# TX_V1_Schematic.net
KiCad netlist of a schematic drawn in Altium Designer
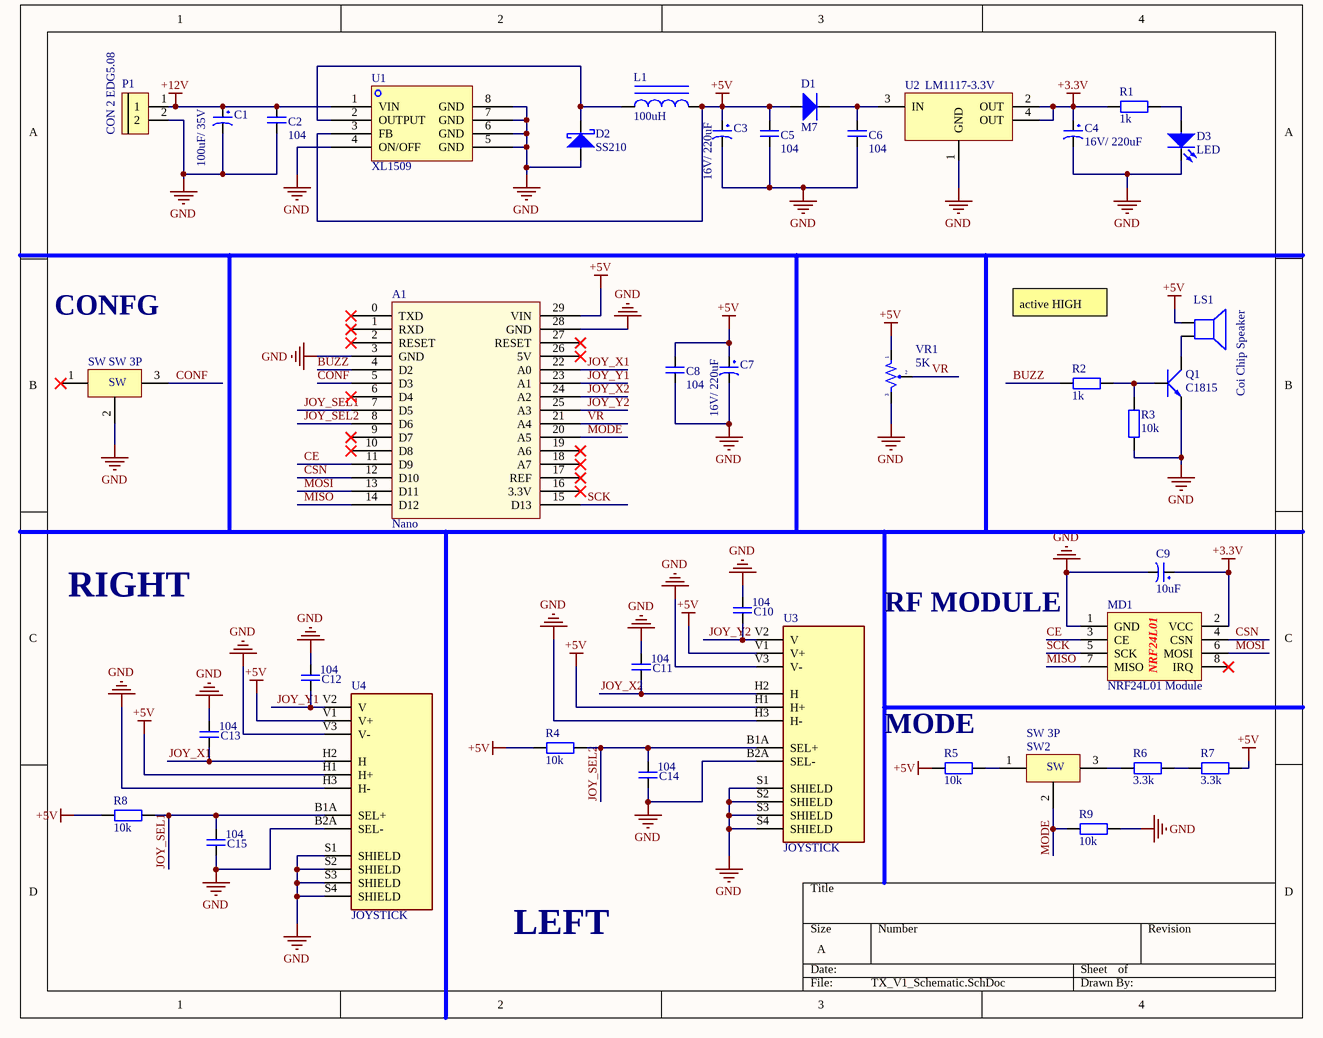
[diagram p0: TX_V1_Schematic.SchDoc]

(export (version "E")
  (design (tool "Eeschema 10.0.6"))
  (components
    (comp (ref "A1")
      (value "Nano")
      (footprint "Arduino nano")
      (libsource (lib "Altium_Lib_by_KhueNguyenCreator") (part "Arduino Nano"))
    )
    (comp (ref "C1")
      (value "100uF/ 35V")
      (footprint "CAP SMD ALUMINUM D8")
      (libsource (lib "Electronic4u") (part "Cap_Polar"))
    )
    (comp (ref "C2")
      (value "104")
      (footprint "SM-0805")
      (libsource (lib "Electronic4u") (part "Cap_Non-Polar"))
    )
    (comp (ref "C3")
      (value "16V/ 220uF")
      (footprint "CAP SMD ALUMINUM D8")
      (libsource (lib "Electronic4u") (part "Cap_Polar"))
    )
    (comp (ref "C4")
      (value "16V/ 220uF")
      (footprint "CAP SMD ALUMINUM D8")
      (libsource (lib "Electronic4u") (part "Cap_Polar"))
    )
    (comp (ref "C5")
      (value "104")
      (footprint "SM-0805")
      (libsource (lib "Electronic4u") (part "Cap_Non-Polar"))
    )
    (comp (ref "C6")
      (value "104")
      (footprint "SM-0805")
      (libsource (lib "Electronic4u") (part "Cap_Non-Polar"))
    )
    (comp (ref "C7")
      (value "16V/ 220uF")
      (footprint "CAP SMD ALUMINUM D8")
      (libsource (lib "Electronic4u") (part "Cap_Polar"))
    )
    (comp (ref "C8")
      (value "104")
      (footprint "SM-0805")
      (libsource (lib "Electronic4u") (part "Cap_Non-Polar"))
    )
    (comp (ref "C9")
      (value "10uF")
      (footprint "tu hoa 8mm")
      (description "Cắm")
      (libsource (lib "Altium_Lib_by_KhueNguyenCreator") (part "Tu Hoa 100uF 35V 8x11"))
    )
    (comp (ref "C10")
      (value "104")
      (footprint "SM-0805")
      (libsource (lib "Electronic4u") (part "Cap_Non-Polar"))
    )
    (comp (ref "C11")
      (value "104")
      (footprint "SM-0805")
      (libsource (lib "Electronic4u") (part "Cap_Non-Polar"))
    )
    (comp (ref "C12")
      (value "104")
      (footprint "SM-0805")
      (libsource (lib "Electronic4u") (part "Cap_Non-Polar"))
    )
    (comp (ref "C13")
      (value "104")
      (footprint "SM-0805")
      (libsource (lib "Electronic4u") (part "Cap_Non-Polar"))
    )
    (comp (ref "C14")
      (value "104")
      (footprint "SM-0805")
      (libsource (lib "Electronic4u") (part "Cap_Non-Polar"))
    )
    (comp (ref "C15")
      (value "104")
      (footprint "SM-0805")
      (libsource (lib "Electronic4u") (part "Cap_Non-Polar"))
    )
    (comp (ref "D1")
      (value "M7")
      (footprint "DO-214AC")
      (description "Diode Standard")
      (fields (field (name "PART NUMBER") "LED 3 ly Single Colour"))
      (libsource (lib "Electronic4u") (part "Diode Standard"))
    )
    (comp (ref "D2")
      (value "SS210")
      (footprint "DO-214AC")
      (description "Diode Schottky")
      (fields (field (name "PART NUMBER") "LED 3 ly Single Colour"))
      (libsource (lib "Electronic4u") (part "Diode Schottky"))
    )
    (comp (ref "D3")
      (value "LED")
      (footprint "LED-3MM GRE")
      (description "LED Single")
      (libsource (lib "Electronic4u") (part "LED"))
    )
    (comp (ref "L1")
      (value "100uH")
      (footprint "INDUCTOR SMD 7342 7.3X7.3X4.2mm")
      (description "Magnetic-Core Inductor")
      (libsource (lib "Electronic4u") (part "Inductor Iron"))
    )
    (comp (ref "LS1")
      (value "Coi Chip Speaker")
      (footprint "Coi Chip Speacker")
      (description "Còi chip")
      (libsource (lib "Altium_Lib_by_KhueNguyenCreator") (part "Coi Chip Speaker"))
    )
    (comp (ref "MD1")
      (value "NRF24L01 Module")
      (footprint "NRF24L01")
      (libsource (lib "Altium_Lib_by_KhueNguyenCreator") (part "NRF24L01 Module"))
    )
    (comp (ref "P1")
      (value "CON 2 EDG5.08")
      (footprint "CON 2 2EDG5.08")
      (description "Cắm")
      (libsource (lib "Altium_Lib_by_KhueNguyenCreator") (part "CON 2 EDG5.08"))
    )
    (comp (ref "Q1")
      (value "C1815")
      (footprint "SOT23B")
      (description "NPN 600mW, ECB")
      (libsource (lib "Electronic4u") (part "C1815"))
    )
    (comp (ref "R1")
      (value "1k")
      (footprint "RESISTOR SMD 0805")
      (libsource (lib "Electronic4u") (part "Resistor"))
    )
    (comp (ref "R2")
      (value "1k")
      (footprint "RESISTOR SMD 0805")
      (libsource (lib "Electronic4u") (part "Resistor"))
    )
    (comp (ref "R3")
      (value "10k")
      (footprint "RESISTOR SMD 0805")
      (libsource (lib "Electronic4u") (part "Resistor"))
    )
    (comp (ref "R4")
      (value "10k")
      (footprint "RESISTOR SMD 0805")
      (libsource (lib "Electronic4u") (part "Resistor"))
    )
    (comp (ref "R5")
      (value "10k")
      (footprint "RESISTOR SMD 0805")
      (libsource (lib "Electronic4u") (part "Resistor"))
    )
    (comp (ref "R6")
      (value "3.3k")
      (footprint "RESISTOR SMD 0805")
      (libsource (lib "Electronic4u") (part "Resistor"))
    )
    (comp (ref "R7")
      (value "3.3k")
      (footprint "RESISTOR SMD 0805")
      (libsource (lib "Electronic4u") (part "Resistor"))
    )
    (comp (ref "R8")
      (value "10k")
      (footprint "RESISTOR SMD 0805")
      (libsource (lib "Electronic4u") (part "Resistor"))
    )
    (comp (ref "R9")
      (value "10k")
      (footprint "RESISTOR SMD 0805")
      (libsource (lib "Electronic4u") (part "Resistor"))
    )
    (comp (ref "SW") (value "SW 3P") (footprint "MTS-102") (libsource (lib "FMS_PcbLib1") (part "SW 3P")))
    (comp (ref "SW2") (value "SW 3P") (footprint "MTS-102") (libsource (lib "FMS_PcbLib1") (part "SW 3P")))
    (comp (ref "U1")
      (value "XL1509")
      (footprint "SOP8")
      (description "IC power sop8")
      (libsource (lib "FMS_PcbLib1") (part "XL1509"))
    )
    (comp (ref "U2")
      (value "LM1117-3.3V")
      (footprint "SOT223-4N")
      (description "800mA Low-Dropout Linear Regulator")
      (fields (field (name "CREATOR") "Nguyen Ba Bien"))
      (libsource (lib "Electronic4u") (part "LM1117"))
    )
    (comp (ref "U3")
      (value "JOYSTICK")
      (footprint "XDCR_COM-09032")
      (description "Thumb Joystick")
      (fields (field (name "MP") "COM-09032"))
      (libsource (lib "FMS_PcbLib1") (part "JOYSTICK"))
    )
    (comp (ref "U4")
      (value "JOYSTICK")
      (footprint "XDCR_COM-09032")
      (description "Thumb Joystick")
      (fields (field (name "MP") "COM-09032"))
      (libsource (lib "FMS_PcbLib1") (part "JOYSTICK"))
    )
    (comp (ref "VR1")
      (value "5K")
      (footprint "Bien Tro Volume Don")
      (description "Cắm")
      (libsource (lib "Altium_Lib_by_KhueNguyenCreator") (part "Triet Ap Don 5k"))
    )
  )
  (nets
    (net (code "1") (name "+3.3V") (class "Default")
      (node (ref "C4") (pin "1") (pinfunction "1_1") (pintype "passive"))
      (node (ref "C9") (pin "1") (pinfunction "1_1") (pintype "passive"))
      (node (ref "MD1") (pin "2") (pinfunction "VCC_2") (pintype "passive"))
      (node (ref "R1") (pin "1") (pinfunction "1_1") (pintype "passive"))
      (node (ref "U2") (pin "2") (pinfunction "OUT_2") (pintype "passive"))
      (node (ref "U2") (pin "4") (pinfunction "OUT_4") (pintype "passive"))
    )
    (net (code "2") (name "+5V") (class "Default")
      (node (ref "A1") (pin "29") (pinfunction "VIN_29") (pintype "passive"))
      (node (ref "C3") (pin "1") (pinfunction "1_1") (pintype "passive"))
      (node (ref "C5") (pin "2") (pinfunction "2_2") (pintype "passive"))
      (node (ref "C7") (pin "1") (pinfunction "1_1") (pintype "passive"))
      (node (ref "C8") (pin "2") (pinfunction "2_2") (pintype "passive"))
      (node (ref "D1") (pin "1") (pinfunction "1_1") (pintype "passive"))
      (node (ref "L1") (pin "2") (pinfunction "2_2") (pintype "passive"))
      (node (ref "LS1") (pin "1") (pinfunction "1_1") (pintype "passive"))
      (node (ref "R4") (pin "1") (pinfunction "1_1") (pintype "passive"))
      (node (ref "R5") (pin "2") (pinfunction "2_2") (pintype "passive"))
      (node (ref "R7") (pin "1") (pinfunction "1_1") (pintype "passive"))
      (node (ref "R8") (pin "1") (pinfunction "1_1") (pintype "passive"))
      (node (ref "U1") (pin "3") (pinfunction "FB_3") (pintype "passive"))
      (node (ref "U3") (pin "H1") (pinfunction "H+_H1") (pintype "passive"))
      (node (ref "U3") (pin "V1") (pinfunction "V+_V1") (pintype "passive"))
      (node (ref "U4") (pin "H1") (pinfunction "H+_H1") (pintype "passive"))
      (node (ref "U4") (pin "V1") (pinfunction "V+_V1") (pintype "passive"))
      (node (ref "VR1") (pin "1") (pinfunction "1_1") (pintype "passive"))
    )
    (net (code "3") (name "+12V") (class "Default")
      (node (ref "C1") (pin "1") (pinfunction "1_1") (pintype "passive"))
      (node (ref "C2") (pin "2") (pinfunction "2_2") (pintype "passive"))
      (node (ref "P1") (pin "1") (pinfunction "1_1") (pintype "passive"))
      (node (ref "U1") (pin "1") (pinfunction "VIN_1") (pintype "passive"))
    )
    (net (code "4") (name "/BUZZ") (class "Default")
      (node (ref "A1") (pin "4") (pinfunction "D2_4") (pintype "passive"))
      (node (ref "R2") (pin "2") (pinfunction "2_2") (pintype "passive"))
    )
    (net (code "5") (name "/CE") (class "Default")
      (node (ref "A1") (pin "11") (pinfunction "D9_11") (pintype "passive"))
      (node (ref "MD1") (pin "3") (pinfunction "CE_3") (pintype "passive"))
    )
    (net (code "6") (name "/CONF") (class "Default")
      (node (ref "A1") (pin "5") (pinfunction "D3_5") (pintype "passive"))
      (node (ref "SW") (pin "3") (pinfunction "3_3") (pintype "passive"))
    )
    (net (code "7") (name "/CSN") (class "Default")
      (node (ref "A1") (pin "12") (pinfunction "D10_12") (pintype "passive"))
      (node (ref "MD1") (pin "4") (pinfunction "CSN_4") (pintype "passive"))
    )
    (net (code "8") (name "/JOY_SEL1") (class "Default")
      (node (ref "A1") (pin "7") (pinfunction "D5_7") (pintype "passive"))
      (node (ref "C15") (pin "2") (pinfunction "2_2") (pintype "passive"))
      (node (ref "R8") (pin "2") (pinfunction "2_2") (pintype "passive"))
      (node (ref "U4") (pin "B1A") (pinfunction "SEL+_B1A") (pintype "passive"))
    )
    (net (code "9") (name "/JOY_SEL2") (class "Default")
      (node (ref "A1") (pin "8") (pinfunction "D6_8") (pintype "passive"))
      (node (ref "C14") (pin "2") (pinfunction "2_2") (pintype "passive"))
      (node (ref "R4") (pin "2") (pinfunction "2_2") (pintype "passive"))
      (node (ref "U3") (pin "B1A") (pinfunction "SEL+_B1A") (pintype "passive"))
    )
    (net (code "10") (name "/JOY_X1") (class "Default")
      (node (ref "A1") (pin "22") (pinfunction "A0_22") (pintype "passive"))
      (node (ref "C13") (pin "1") (pinfunction "1_1") (pintype "passive"))
      (node (ref "U4") (pin "H2") (pinfunction "H_H2") (pintype "passive"))
    )
    (net (code "11") (name "/JOY_X2") (class "Default")
      (node (ref "A1") (pin "24") (pinfunction "A2_24") (pintype "passive"))
      (node (ref "C11") (pin "1") (pinfunction "1_1") (pintype "passive"))
      (node (ref "U3") (pin "H2") (pinfunction "H_H2") (pintype "passive"))
    )
    (net (code "12") (name "/JOY_Y1") (class "Default")
      (node (ref "A1") (pin "23") (pinfunction "A1_23") (pintype "passive"))
      (node (ref "C12") (pin "1") (pinfunction "1_1") (pintype "passive"))
      (node (ref "U4") (pin "V2") (pinfunction "V_V2") (pintype "passive"))
    )
    (net (code "13") (name "/JOY_Y2") (class "Default")
      (node (ref "A1") (pin "25") (pinfunction "A3_25") (pintype "passive"))
      (node (ref "C10") (pin "1") (pinfunction "1_1") (pintype "passive"))
      (node (ref "U3") (pin "V2") (pinfunction "V_V2") (pintype "passive"))
    )
    (net (code "14") (name "/MISO") (class "Default")
      (node (ref "A1") (pin "14") (pinfunction "D12_14") (pintype "passive"))
      (node (ref "MD1") (pin "7") (pinfunction "MISO_7") (pintype "passive"))
    )
    (net (code "15") (name "/MODE") (class "Default")
      (node (ref "A1") (pin "20") (pinfunction "A5_20") (pintype "passive"))
      (node (ref "R9") (pin "2") (pinfunction "2_2") (pintype "passive"))
      (node (ref "SW2") (pin "2") (pinfunction "2_2") (pintype "passive"))
    )
    (net (code "16") (name "/MOSI") (class "Default")
      (node (ref "A1") (pin "13") (pinfunction "D11_13") (pintype "passive"))
      (node (ref "MD1") (pin "6") (pinfunction "MOSI_6") (pintype "passive"))
    )
    (net (code "17") (name "/SCK") (class "Default")
      (node (ref "A1") (pin "15") (pinfunction "D13_15") (pintype "passive"))
      (node (ref "MD1") (pin "5") (pinfunction "SCK_5") (pintype "passive"))
    )
    (net (code "18") (name "/VR") (class "Default")
      (node (ref "A1") (pin "21") (pinfunction "A4_21") (pintype "passive"))
      (node (ref "VR1") (pin "2") (pinfunction "2_2") (pintype "passive"))
    )
    (net (code "19") (name "GND") (class "Default")
      (node (ref "A1") (pin "28") (pinfunction "GND_28") (pintype "passive"))
      (node (ref "A1") (pin "3") (pinfunction "GND_3") (pintype "passive"))
      (node (ref "C1") (pin "2") (pinfunction "2_2") (pintype "passive"))
      (node (ref "C10") (pin "2") (pinfunction "2_2") (pintype "passive"))
      (node (ref "C11") (pin "2") (pinfunction "2_2") (pintype "passive"))
      (node (ref "C12") (pin "2") (pinfunction "2_2") (pintype "passive"))
      (node (ref "C13") (pin "2") (pinfunction "2_2") (pintype "passive"))
      (node (ref "C14") (pin "1") (pinfunction "1_1") (pintype "passive"))
      (node (ref "C15") (pin "1") (pinfunction "1_1") (pintype "passive"))
      (node (ref "C2") (pin "1") (pinfunction "1_1") (pintype "passive"))
      (node (ref "C3") (pin "2") (pinfunction "2_2") (pintype "passive"))
      (node (ref "C4") (pin "2") (pinfunction "2_2") (pintype "passive"))
      (node (ref "C5") (pin "1") (pinfunction "1_1") (pintype "passive"))
      (node (ref "C6") (pin "1") (pinfunction "1_1") (pintype "passive"))
      (node (ref "C7") (pin "2") (pinfunction "2_2") (pintype "passive"))
      (node (ref "C8") (pin "1") (pinfunction "1_1") (pintype "passive"))
      (node (ref "C9") (pin "2") (pinfunction "2_2") (pintype "passive"))
      (node (ref "D2") (pin "1") (pinfunction "1_1") (pintype "passive"))
      (node (ref "D3") (pin "2") (pinfunction "2_2") (pintype "passive"))
      (node (ref "MD1") (pin "1") (pinfunction "GND_1") (pintype "passive"))
      (node (ref "P1") (pin "2") (pinfunction "2_2") (pintype "passive"))
      (node (ref "Q1") (pin "1") (pinfunction "E_1") (pintype "passive"))
      (node (ref "R3") (pin "2") (pinfunction "2_2") (pintype "passive"))
      (node (ref "R9") (pin "1") (pinfunction "1_1") (pintype "passive"))
      (node (ref "SW") (pin "2") (pinfunction "2_2") (pintype "passive"))
      (node (ref "U1") (pin "4") (pinfunction "ON/OFF_4") (pintype "passive"))
      (node (ref "U1") (pin "5") (pinfunction "GND_5") (pintype "passive"))
      (node (ref "U1") (pin "6") (pinfunction "GND_6") (pintype "passive"))
      (node (ref "U1") (pin "7") (pinfunction "GND_7") (pintype "passive"))
      (node (ref "U1") (pin "8") (pinfunction "GND_8") (pintype "passive"))
      (node (ref "U2") (pin "1") (pinfunction "GND_1") (pintype "passive"))
      (node (ref "U3") (pin "B2A") (pinfunction "SEL-_B2A") (pintype "passive"))
      (node (ref "U3") (pin "H3") (pinfunction "H-_H3") (pintype "passive"))
      (node (ref "U3") (pin "S1") (pinfunction "SHIELD_S1") (pintype "passive"))
      (node (ref "U3") (pin "S2") (pinfunction "SHIELD_S2") (pintype "passive"))
      (node (ref "U3") (pin "S3") (pinfunction "SHIELD_S3") (pintype "passive"))
      (node (ref "U3") (pin "S4") (pinfunction "SHIELD_S4") (pintype "passive"))
      (node (ref "U3") (pin "V3") (pinfunction "V-_V3") (pintype "passive"))
      (node (ref "U4") (pin "B2A") (pinfunction "SEL-_B2A") (pintype "passive"))
      (node (ref "U4") (pin "H3") (pinfunction "H-_H3") (pintype "passive"))
      (node (ref "U4") (pin "S1") (pinfunction "SHIELD_S1") (pintype "passive"))
      (node (ref "U4") (pin "S2") (pinfunction "SHIELD_S2") (pintype "passive"))
      (node (ref "U4") (pin "S3") (pinfunction "SHIELD_S3") (pintype "passive"))
      (node (ref "U4") (pin "S4") (pinfunction "SHIELD_S4") (pintype "passive"))
      (node (ref "U4") (pin "V3") (pinfunction "V-_V3") (pintype "passive"))
      (node (ref "VR1") (pin "3") (pinfunction "3_3") (pintype "passive"))
    )
    (net (code "20") (name "Net-(D3-Pad1)") (class "Default")
      (node (ref "D3") (pin "1") (pinfunction "1_1") (pintype "passive"))
      (node (ref "R1") (pin "2") (pinfunction "2_2") (pintype "passive"))
    )
    (net (code "21") (name "Net-(Q1-B)") (class "Default")
      (node (ref "Q1") (pin "3") (pinfunction "B_3") (pintype "passive"))
      (node (ref "R2") (pin "1") (pinfunction "1_1") (pintype "passive"))
      (node (ref "R3") (pin "1") (pinfunction "1_1") (pintype "passive"))
    )
    (net (code "22") (name "Net-(Q1-C)") (class "Default")
      (node (ref "LS1") (pin "2") (pinfunction "2_2") (pintype "passive"))
      (node (ref "Q1") (pin "2") (pinfunction "C_2") (pintype "passive"))
    )
    (net (code "23") (name "Net-(R5-Pad1)") (class "Default")
      (node (ref "R5") (pin "1") (pinfunction "1_1") (pintype "passive"))
      (node (ref "SW2") (pin "1") (pinfunction "1_1") (pintype "passive"))
    )
    (net (code "24") (name "Net-(R6-Pad1)") (class "Default")
      (node (ref "R6") (pin "1") (pinfunction "1_1") (pintype "passive"))
      (node (ref "R7") (pin "2") (pinfunction "2_2") (pintype "passive"))
    )
    (net (code "25") (name "Net-(R6-Pad2)") (class "Default")
      (node (ref "R6") (pin "2") (pinfunction "2_2") (pintype "passive"))
      (node (ref "SW2") (pin "3") (pinfunction "3_3") (pintype "passive"))
    )
    (net (code "26") (name "Net-(U1-OUTPUT)") (class "Default")
      (node (ref "D2") (pin "2") (pinfunction "2_2") (pintype "passive"))
      (node (ref "L1") (pin "1") (pinfunction "1_1") (pintype "passive"))
      (node (ref "U1") (pin "2") (pinfunction "OUTPUT_2") (pintype "passive"))
    )
    (net (code "27") (name "Net-(U2-IN)") (class "Default")
      (node (ref "C6") (pin "2") (pinfunction "2_2") (pintype "passive"))
      (node (ref "D1") (pin "2") (pinfunction "2_2") (pintype "passive"))
      (node (ref "U2") (pin "3") (pinfunction "IN_3") (pintype "passive"))
    )
    (net (code "28") (name "unconnected-(A1-3.3V-Pad16)") (class "Default")
      (node (ref "A1") (pin "16") (pinfunction "3.3V_16") (pintype "passive+no_connect"))
    )
    (net (code "29") (name "unconnected-(A1-5V-Pad26)") (class "Default")
      (node (ref "A1") (pin "26") (pinfunction "5V_26") (pintype "passive+no_connect"))
    )
    (net (code "30") (name "unconnected-(A1-A6-Pad19)") (class "Default")
      (node (ref "A1") (pin "19") (pinfunction "A6_19") (pintype "passive+no_connect"))
    )
    (net (code "31") (name "unconnected-(A1-A7-Pad18)") (class "Default")
      (node (ref "A1") (pin "18") (pinfunction "A7_18") (pintype "passive+no_connect"))
    )
    (net (code "32") (name "unconnected-(A1-D4-Pad6)") (class "Default")
      (node (ref "A1") (pin "6") (pinfunction "D4_6") (pintype "passive+no_connect"))
    )
    (net (code "33") (name "unconnected-(A1-D7-Pad9)") (class "Default")
      (node (ref "A1") (pin "9") (pinfunction "D7_9") (pintype "passive+no_connect"))
    )
    (net (code "34") (name "unconnected-(A1-D8-Pad10)") (class "Default")
      (node (ref "A1") (pin "10") (pinfunction "D8_10") (pintype "passive+no_connect"))
    )
    (net (code "35") (name "unconnected-(A1-REF-Pad17)") (class "Default")
      (node (ref "A1") (pin "17") (pinfunction "REF_17") (pintype "passive+no_connect"))
    )
    (net (code "36") (name "unconnected-(A1-RESET-Pad2)") (class "Default")
      (node (ref "A1") (pin "2") (pinfunction "RESET_2") (pintype "passive+no_connect"))
    )
    (net (code "37") (name "unconnected-(A1-RESET-Pad27)") (class "Default")
      (node (ref "A1") (pin "27") (pinfunction "RESET_27") (pintype "passive+no_connect"))
    )
    (net (code "38") (name "unconnected-(A1-RXD-Pad1)") (class "Default")
      (node (ref "A1") (pin "1") (pinfunction "RXD_1") (pintype "passive+no_connect"))
    )
    (net (code "39") (name "unconnected-(A1-TXD-Pad0)") (class "Default")
      (node (ref "A1") (pin "0") (pinfunction "TXD_0") (pintype "passive+no_connect"))
    )
    (net (code "40") (name "unconnected-(MD1-IRQ-Pad8)") (class "Default")
      (node (ref "MD1") (pin "8") (pinfunction "IRQ_8") (pintype "passive+no_connect"))
    )
    (net (code "41") (name "unconnected-(SW-Pad1)") (class "Default")
      (node (ref "SW") (pin "1") (pinfunction "1_1") (pintype "passive+no_connect"))
    )
  )
)
